# AMP1.net
KiCad netlist of a schematic drawn in Altium Designer
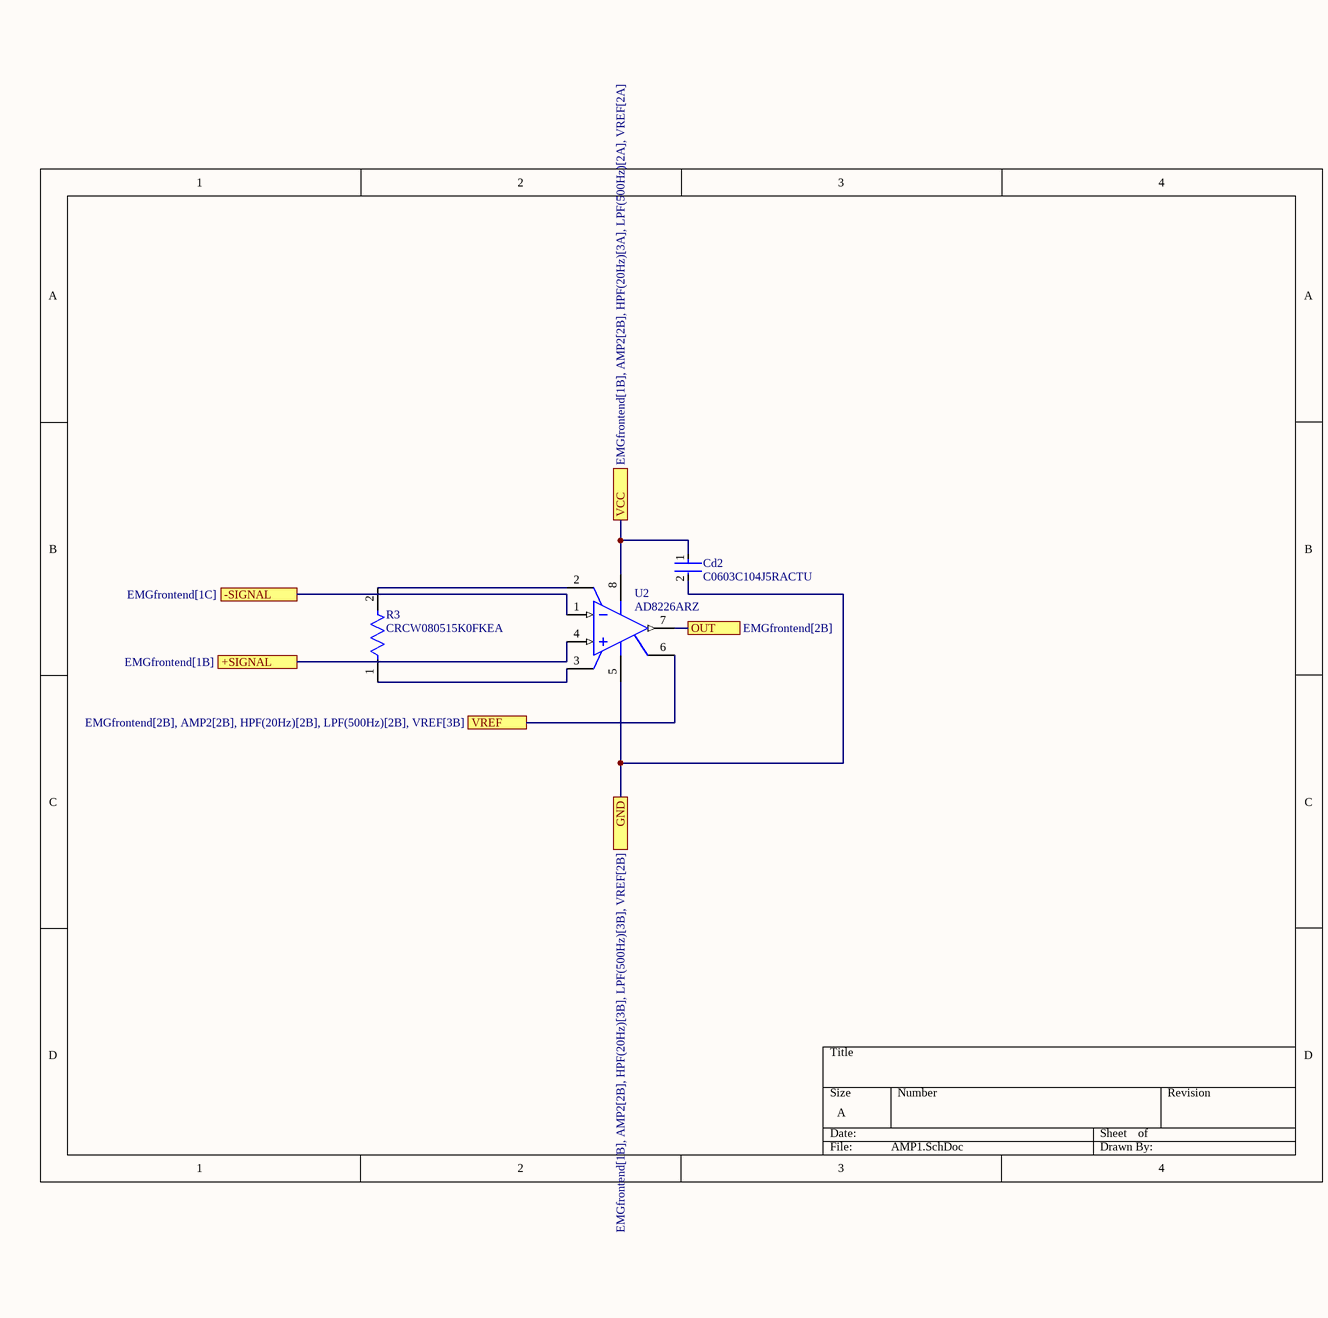
[diagram p0: AMP1.SchDoc]

(export (version "E")
  (design (tool "Eeschema 10.0.6"))
  (components
    (comp (ref "Cd2")
      (value "C0603C104J5RACTU")
      (footprint "FP-C0603C-CF-MFG")
      (description "CAP CER 0.1UF 50V 5% X7R 0603")
      (fields
        (field (name "TOLERANCE") "0.05")
        (field (name "OCTOPART") "https://octopart.com/c0603c104j5ractu-kemet-10440638")
      )
      (libsource (lib "Altium Content Vault") (part "b4654b650e69147ec39a6b967a45e02"))
    )
    (comp (ref "R3")
      (value "CRCW080515K0FKEA")
      (footprint "FP-CRCW0805-e3-IPC_C")
      (description "RES Thick Film, 15kΩ, 1%, 0.125W, 100ppm/°C, 0805")
      (fields (field (name "TOLERANCE") "1%"))
      (libsource (lib "Altium Content Vault") (part "1029c3af85768c4190bb7ad29bc67b5"))
    )
    (comp (ref "U2")
      (value "AD8226ARZ")
      (footprint "ADI-R-8_L")
      (fields (field (name "MANUFACTURER") "Analog Devices"))
      (libsource (lib "Altium Content Vault") (part "ADI-AD8226-R-8"))
    )
  )
  (nets
    (net (code "1") (name "/+SIGNAL") (class "Default")
      (node (ref "U2") (pin "4") (pinfunction "+IN_4") (pintype "input"))
    )
    (net (code "2") (name "/-SIGNAL") (class "Default")
      (node (ref "U2") (pin "1") (pinfunction "-IN_1") (pintype "input"))
    )
    (net (code "3") (name "/GND") (class "Default")
      (node (ref "Cd2") (pin "2") (pinfunction "2_2") (pintype "passive"))
      (node (ref "U2") (pin "5") (pinfunction "-VS_5") (pintype "power_in"))
    )
    (net (code "4") (name "/OUT") (class "Default")
      (node (ref "U2") (pin "7") (pinfunction "VOUT_7") (pintype "output"))
    )
    (net (code "5") (name "/VCC") (class "Default")
      (node (ref "Cd2") (pin "1") (pinfunction "1_1") (pintype "passive"))
      (node (ref "U2") (pin "8") (pinfunction "+VS_8") (pintype "power_in"))
    )
    (net (code "6") (name "/VREF") (class "Default")
      (node (ref "U2") (pin "6") (pinfunction "REF_6") (pintype "passive"))
    )
    (net (code "7") (name "Net-(R3-Pad1)") (class "Default")
      (node (ref "R3") (pin "1") (pinfunction "1_1") (pintype "passive"))
      (node (ref "U2") (pin "3") (pinfunction "RG_3") (pintype "passive"))
    )
    (net (code "8") (name "Net-(R3-Pad2)") (class "Default")
      (node (ref "R3") (pin "2") (pinfunction "2_2") (pintype "passive"))
      (node (ref "U2") (pin "2") (pinfunction "RG_2") (pintype "passive"))
    )
  )
)
